# PM-BAT_v1_0-35X22_86.net
KiCad netlist of a schematic drawn in EAGLE
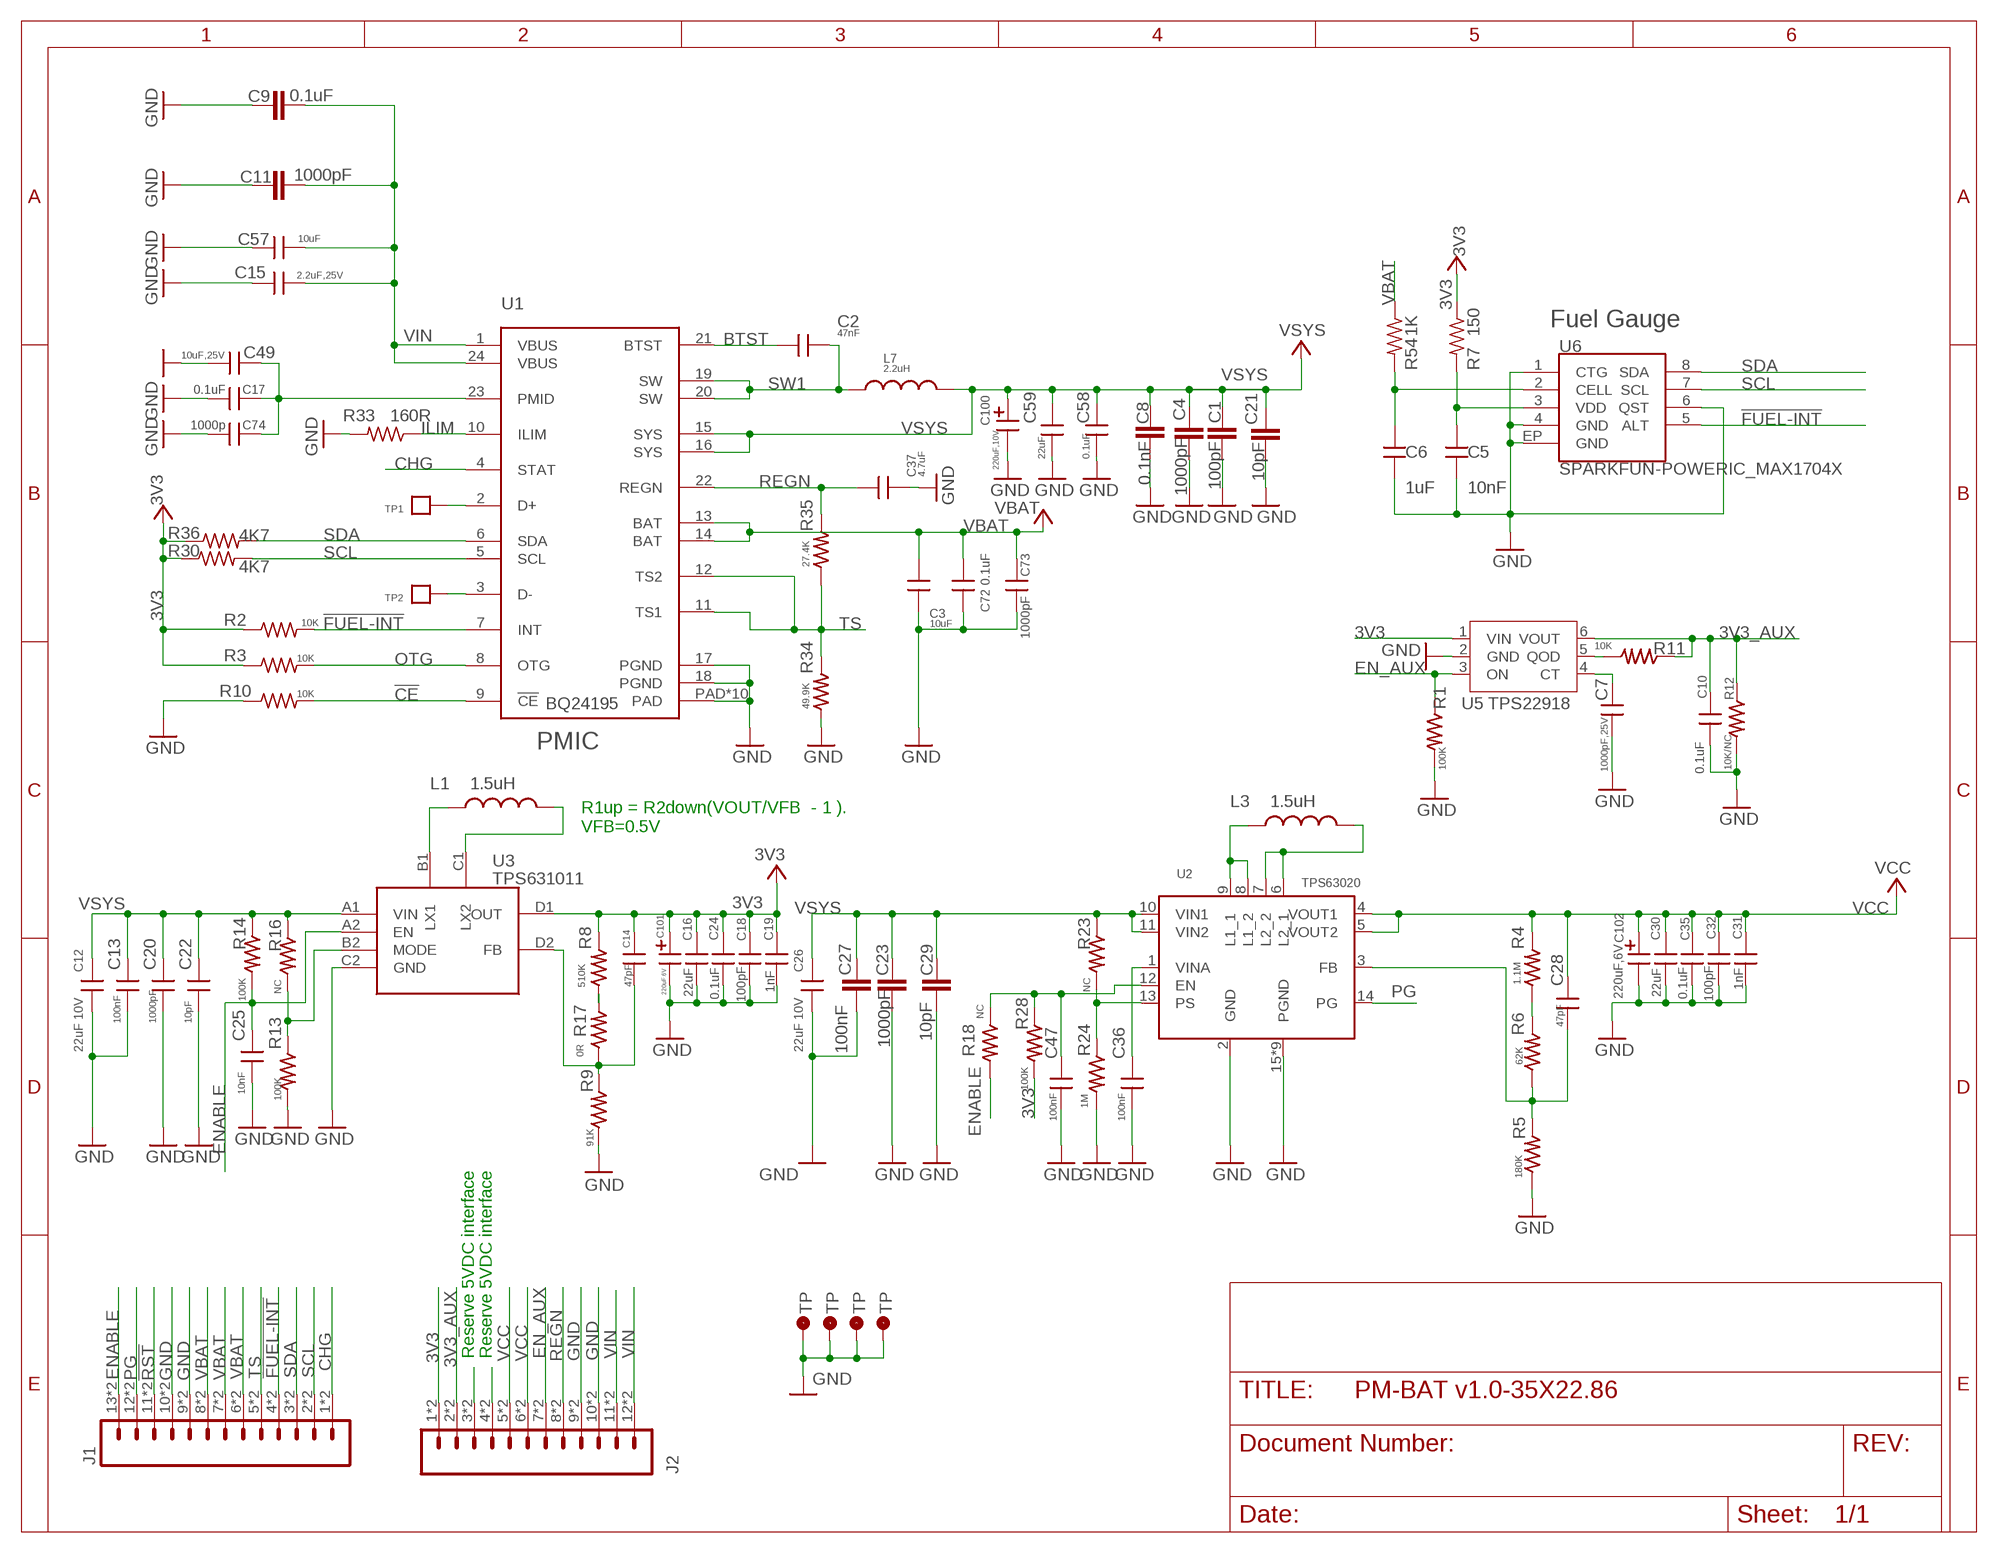
[diagram p0: schematic, sheet 1]

(export (version "E")
  (design (tool "Eeschema 10.0.6"))
  (components
    (comp (ref "C1")
      (value "100pF")
      (footprint "eagle-import:C0402_B")
      (libsource (lib "eagle-import") (part "CAP_1"))
    )
    (comp (ref "C2")
      (value "47nF")
      (footprint "eagle-import:C-0402")
      (libsource (lib "eagle-import") (part "particle SZ_CAP0402"))
    )
    (comp (ref "C3")
      (value "10uF")
      (footprint "eagle-import:C0805")
      (libsource (lib "eagle-import") (part "particle SZ_CAPC0805"))
    )
    (comp (ref "C4")
      (value "1000pF")
      (footprint "eagle-import:C0402_B")
      (libsource (lib "eagle-import") (part "CAP_1"))
    )
    (comp (ref "C5")
      (value "10nF")
      (footprint "eagle-import:C0402")
      (libsource (lib "eagle-import") (part "particle SZ_CAP0402A"))
    )
    (comp (ref "C6")
      (value "1uF")
      (footprint "eagle-import:C0402")
      (libsource (lib "eagle-import") (part "particle SZ_CAP0402A"))
    )
    (comp (ref "C7")
      (value "1000pF,25V")
      (footprint "eagle-import:C0402")
      (libsource (lib "eagle-import") (part "particle SZ_CAP0402A"))
    )
    (comp (ref "C8")
      (value "0.1nF")
      (footprint "eagle-import:C0402_B")
      (libsource (lib "eagle-import") (part "CAP_1"))
    )
    (comp (ref "C9")
      (value "0.1uF")
      (footprint "eagle-import:C0402_B")
      (libsource (lib "eagle-import") (part "CAP_1"))
    )
    (comp (ref "C10")
      (value "0.1uF")
      (footprint "eagle-import:C0201-N")
      (libsource (lib "eagle-import") (part "CAPC0201-N"))
    )
    (comp (ref "C11")
      (value "1000pF")
      (footprint "eagle-import:C0402_B")
      (libsource (lib "eagle-import") (part "CAP_1"))
    )
    (comp (ref "C12")
      (value "22uF 10V")
      (footprint "eagle-import:C0603")
      (libsource (lib "eagle-import") (part "particle SZ_21650216_CAPC0603"))
    )
    (comp (ref "C13")
      (value "100nF")
      (footprint "eagle-import:C0201-N")
      (libsource (lib "eagle-import") (part "CAPC0201-N"))
    )
    (comp (ref "C14")
      (value "47pF")
      (footprint "eagle-import:C0201-N")
      (libsource (lib "eagle-import") (part "CAPC0201-N"))
    )
    (comp (ref "C15")
      (value "2.2uF,25V")
      (footprint "eagle-import:C-0603A")
      (libsource (lib "eagle-import") (part "particle SZ_CAP0603A"))
    )
    (comp (ref "C16")
      (value "22uF")
      (footprint "eagle-import:C-0603A")
      (libsource (lib "eagle-import") (part "particle SZ_21650216_CAP0603A"))
    )
    (comp (ref "C17")
      (value "0.1uF")
      (footprint "eagle-import:C0402")
      (libsource (lib "eagle-import") (part "CAP0402A"))
    )
    (comp (ref "C18")
      (value "100pF")
      (footprint "eagle-import:C0402")
      (libsource (lib "eagle-import") (part "particle SZ_CAP0402A"))
    )
    (comp (ref "C19")
      (value "1nF")
      (footprint "eagle-import:C0402")
      (libsource (lib "eagle-import") (part "particle SZ_CAP0402A"))
    )
    (comp (ref "C20")
      (value "1000pF")
      (footprint "eagle-import:C0201-N")
      (libsource (lib "eagle-import") (part "CAPC0201-N"))
    )
    (comp (ref "C21")
      (value "10pF")
      (footprint "eagle-import:C0402_B")
      (libsource (lib "eagle-import") (part "CAP_1"))
    )
    (comp (ref "C22")
      (value "10pF")
      (footprint "eagle-import:C0201-N")
      (libsource (lib "eagle-import") (part "CAPC0201-N"))
    )
    (comp (ref "C23")
      (value "1000pF")
      (footprint "eagle-import:C0402_B")
      (libsource (lib "eagle-import") (part "CAP_1"))
    )
    (comp (ref "C24")
      (value "0.1uF")
      (footprint "eagle-import:C0402")
      (libsource (lib "eagle-import") (part "particle SZ_CAP0402A"))
    )
    (comp (ref "C25")
      (value "10nF")
      (footprint "eagle-import:C0201-N")
      (libsource (lib "eagle-import") (part "CAPC0201-N"))
    )
    (comp (ref "C26")
      (value "22uF 10V")
      (footprint "eagle-import:C0603")
      (libsource (lib "eagle-import") (part "particle SZ_21650216_CAPC0603"))
    )
    (comp (ref "C27")
      (value "100nF")
      (footprint "eagle-import:C0402_B")
      (libsource (lib "eagle-import") (part "CAP_1"))
    )
    (comp (ref "C28")
      (value "47pF")
      (footprint "eagle-import:C0201-N")
      (libsource (lib "eagle-import") (part "CAPC0201-N"))
    )
    (comp (ref "C29")
      (value "10pF")
      (footprint "eagle-import:C0402_B")
      (libsource (lib "eagle-import") (part "CAP_1"))
    )
    (comp (ref "C30")
      (value "22uF")
      (footprint "eagle-import:C-0603A")
      (libsource (lib "eagle-import") (part "particle SZ_21650216_CAP0603A"))
    )
    (comp (ref "C31")
      (value "1nF")
      (footprint "eagle-import:C0402")
      (libsource (lib "eagle-import") (part "particle SZ_CAP0402A"))
    )
    (comp (ref "C32")
      (value "100pF")
      (footprint "eagle-import:C0402")
      (libsource (lib "eagle-import") (part "particle SZ_CAP0402A"))
    )
    (comp (ref "C35")
      (value "0.1uF")
      (footprint "eagle-import:C0402")
      (libsource (lib "eagle-import") (part "particle SZ_CAP0402A"))
    )
    (comp (ref "C36")
      (value "100nF")
      (footprint "eagle-import:C0201-N")
      (libsource (lib "eagle-import") (part "CAPC0201-N"))
    )
    (comp (ref "C37")
      (value "4.7uF")
      (footprint "eagle-import:C0402")
      (libsource (lib "eagle-import") (part "particle SZ_CAP0402A"))
    )
    (comp (ref "C47")
      (value "100nF")
      (footprint "eagle-import:C0201-N")
      (libsource (lib "eagle-import") (part "CAPC0201-N"))
    )
    (comp (ref "C49")
      (value "10uF,25V")
      (footprint "eagle-import:C-0603A")
      (libsource (lib "eagle-import") (part "particle SZ_CAP0603A"))
    )
    (comp (ref "C57")
      (value "10uF")
      (footprint "eagle-import:C-0603A")
      (libsource (lib "eagle-import") (part "particle SZ_CAP0603A"))
    )
    (comp (ref "C58")
      (value "0.1uF")
      (footprint "eagle-import:C0402")
      (libsource (lib "eagle-import") (part "particle SZ_CAP0402A"))
    )
    (comp (ref "C59")
      (value "22uF")
      (footprint "eagle-import:C0603")
      (libsource (lib "eagle-import") (part "particle SZ_CAPC0603"))
    )
    (comp (ref "C72")
      (value "0.1uF")
      (footprint "eagle-import:C-0402")
      (libsource (lib "eagle-import") (part "particle SZ_CAP0402"))
    )
    (comp (ref "C73")
      (value "1000pF")
      (footprint "eagle-import:C-0402")
      (libsource (lib "eagle-import") (part "particle SZ_CAP0402"))
    )
    (comp (ref "C74")
      (value "1000p")
      (footprint "eagle-import:C-0402")
      (libsource (lib "eagle-import") (part "particle SZ_CAP0402"))
    )
    (comp (ref "C100")
      (value "220uF,10V")
      (footprint "eagle-import:CASE-B")
      (libsource (lib "eagle-import") (part "CAP-ECASE_B"))
    )
    (comp (ref "C101")
      (value "220uF.6V")
      (footprint "eagle-import:CASE-B")
      (libsource (lib "eagle-import") (part "CAP-ECASE_B"))
    )
    (comp (ref "C102")
      (value "220uF,6V")
      (footprint "eagle-import:CASE-B")
      (libsource (lib "eagle-import") (part "CAP-ECASE_B"))
    )
    (comp (ref "J1")
      (value "M13PTH-CST-R")
      (footprint "eagle-import:1X13-CASTELLATED")
      (libsource (lib "eagle-import") (part "M13PTH-CST-R"))
    )
    (comp (ref "J2")
      (value "M12PTH-CST-R")
      (footprint "eagle-import:1X12-CASTELLATED")
      (libsource (lib "eagle-import") (part "M12PTH-CST-R"))
    )
    (comp (ref "L1")
      (value "1.5uH")
      (footprint "eagle-import:INDUCTOR-2520")
      (libsource (lib "eagle-import") (part "INDUCTOR-SPARKFUNINDUCTOR-2520"))
    )
    (comp (ref "L3")
      (value "1.5uH")
      (footprint "eagle-import:INDUCTOR-2520")
      (libsource (lib "eagle-import") (part "INDUCTOR-SPARKFUNINDUCTOR-2520"))
    )
    (comp (ref "L7")
      (value "2.2uH")
      (footprint "eagle-import:INDUCTOR-4040")
      (libsource (lib "eagle-import") (part "INDUCTORI"))
    )
    (comp (ref "R1")
      (value "100K")
      (footprint "eagle-import:R0201-N")
      (libsource (lib "eagle-import") (part "RESR0201-N"))
    )
    (comp (ref "R2")
      (value "10K")
      (footprint "eagle-import:R0402_B")
      (libsource (lib "eagle-import") (part "Spark_R-US_"))
    )
    (comp (ref "R3")
      (value "10K")
      (footprint "eagle-import:R0402_B")
      (libsource (lib "eagle-import") (part "Spark_R-US_"))
    )
    (comp (ref "R4")
      (value "1.1M")
      (footprint "eagle-import:R0201-N")
      (libsource (lib "eagle-import") (part "RESR0201-N"))
    )
    (comp (ref "R5")
      (value "180K")
      (footprint "eagle-import:R0201-N")
      (libsource (lib "eagle-import") (part "RESR0201-N"))
    )
    (comp (ref "R6")
      (value "62K")
      (footprint "eagle-import:R0201-N")
      (libsource (lib "eagle-import") (part "RESR0201-N"))
    )
    (comp (ref "R7")
      (value "150")
      (footprint "eagle-import:R0402_B")
      (libsource (lib "eagle-import") (part "R-US_"))
    )
    (comp (ref "R8")
      (value "510K")
      (footprint "eagle-import:R0201-N")
      (libsource (lib "eagle-import") (part "RESR0201-N"))
    )
    (comp (ref "R9")
      (value "91K")
      (footprint "eagle-import:R0201-N")
      (libsource (lib "eagle-import") (part "RESR0201-N"))
    )
    (comp (ref "R10")
      (value "10K")
      (footprint "eagle-import:R0402_B")
      (libsource (lib "eagle-import") (part "Spark_R-US_"))
    )
    (comp (ref "R11")
      (value "10K")
      (footprint "eagle-import:R0201-N")
      (libsource (lib "eagle-import") (part "RESR0201-N"))
    )
    (comp (ref "R12")
      (value "10K/NC")
      (footprint "eagle-import:R0201-N")
      (libsource (lib "eagle-import") (part "RESR0201-N"))
    )
    (comp (ref "R13")
      (value "100K")
      (footprint "eagle-import:R0201-N")
      (libsource (lib "eagle-import") (part "RESR0201-N"))
    )
    (comp (ref "R14")
      (value "100K")
      (footprint "eagle-import:R0201-N")
      (libsource (lib "eagle-import") (part "RESR0201-N"))
    )
    (comp (ref "R16")
      (value "NC")
      (footprint "eagle-import:R0201-N")
      (libsource (lib "eagle-import") (part "RESR0201-N"))
    )
    (comp (ref "R17")
      (value "0R")
      (footprint "eagle-import:R0201-N")
      (libsource (lib "eagle-import") (part "RESR0201-N"))
    )
    (comp (ref "R18")
      (value "NC")
      (footprint "eagle-import:R0201-N")
      (libsource (lib "eagle-import") (part "RESR0201-N"))
    )
    (comp (ref "R23")
      (value "NC")
      (footprint "eagle-import:R0201-N")
      (libsource (lib "eagle-import") (part "RESR0201-N"))
    )
    (comp (ref "R24")
      (value "1M")
      (footprint "eagle-import:R0201-N")
      (libsource (lib "eagle-import") (part "RESR0201-N"))
    )
    (comp (ref "R28")
      (value "100K")
      (footprint "eagle-import:R0201-N")
      (libsource (lib "eagle-import") (part "RESR0201-N"))
    )
    (comp (ref "R30")
      (value "4K7")
      (footprint "eagle-import:R0402_B")
      (libsource (lib "eagle-import") (part "R-US_"))
    )
    (comp (ref "R33")
      (value "160R")
      (footprint "eagle-import:R0402_B")
      (libsource (lib "eagle-import") (part "R-US_"))
    )
    (comp (ref "R34")
      (value "49.9K")
      (footprint "eagle-import:R0201-N")
      (libsource (lib "eagle-import") (part "RESR0201-N"))
    )
    (comp (ref "R35")
      (value "27.4K")
      (footprint "eagle-import:R0201-N")
      (libsource (lib "eagle-import") (part "RESR0201-N"))
    )
    (comp (ref "R36")
      (value "4K7")
      (footprint "eagle-import:R0402_B")
      (libsource (lib "eagle-import") (part "R-US_"))
    )
    (comp (ref "R54")
      (value "1K")
      (footprint "eagle-import:R0402_B")
      (libsource (lib "eagle-import") (part "R-US_"))
    )
    (comp (ref "TP1")
      (value "TP1311MM")
      (footprint "eagle-import:TP-1311MM")
      (libsource (lib "eagle-import") (part "TP1311MM"))
    )
    (comp (ref "TP2")
      (value "TP1311MM")
      (footprint "eagle-import:TP-1311MM")
      (libsource (lib "eagle-import") (part "TP1311MM"))
    )
    (comp (ref "U$1")
      (value "TP")
      (footprint "eagle-import:TP_2.33X1.37")
      (libsource (lib "eagle-import") (part "TP"))
    )
    (comp (ref "U$2")
      (value "TP")
      (footprint "eagle-import:TP_2.33X1.37")
      (libsource (lib "eagle-import") (part "TP"))
    )
    (comp (ref "U$4")
      (value "TP")
      (footprint "eagle-import:TP_2.33X1.37")
      (libsource (lib "eagle-import") (part "TP"))
    )
    (comp (ref "U$5")
      (value "TP")
      (footprint "eagle-import:TP_2.33X1.37")
      (libsource (lib "eagle-import") (part "TP"))
    )
    (comp (ref "U1")
      (value "BQ24195")
      (footprint "eagle-import:ELECTRON_QFN24")
      (libsource (lib "eagle-import") (part "ELECTRON_BQ24298RTWR"))
    )
    (comp (ref "U2")
      (value "TPS63020")
      (footprint "eagle-import:TPS63020")
      (libsource (lib "eagle-import") (part "TPS63020"))
    )
    (comp (ref "U3")
      (value "TPS631011")
      (footprint "eagle-import:DSBGA")
      (libsource (lib "eagle-import") (part "TPS631010"))
    )
    (comp (ref "U5")
      (value "TPS22918")
      (footprint "eagle-import:SOT-23-6")
      (libsource (lib "eagle-import") (part "TPS22918"))
    )
    (comp (ref "U6")
      (value "SPARKFUN-POWERIC_MAX1704X")
      (footprint "eagle-import:SPARKFUN-POWERIC_TDFN-8")
      (libsource (lib "eagle-import") (part "SPARKFUN-POWERIC_MAX1704X"))
    )
  )
  (nets
    (net (code "1") (name "/3V3_AUX") (class "Default")
      (node (ref "C10") (pin "1") (pinfunction "1_1") (pintype "bidirectional"))
      (node (ref "J2") (pin "2") (pinfunction "2_2") (pintype "passive"))
      (node (ref "J2") (pin "@2") (pinfunction "2_@2") (pintype "passive"))
      (node (ref "R11") (pin "1") (pinfunction "1_1") (pintype "bidirectional"))
      (node (ref "R12") (pin "1") (pinfunction "1_1") (pintype "bidirectional"))
      (node (ref "U5") (pin "6") (pinfunction "VOUT_6") (pintype "bidirectional"))
    )
    (net (code "2") (name "/BTST") (class "Default")
      (node (ref "C2") (pin "1") (pinfunction "1_1") (pintype "bidirectional"))
      (node (ref "U1") (pin "21") (pinfunction "BTST_21") (pintype "bidirectional"))
    )
    (net (code "3") (name "/CHG") (class "Default")
      (node (ref "J1") (pin "1") (pinfunction "1_1") (pintype "passive"))
      (node (ref "J1") (pin "@1") (pinfunction "1_@1") (pintype "passive"))
      (node (ref "U1") (pin "4") (pinfunction "STAT_4") (pintype "bidirectional"))
    )
    (net (code "4") (name "/ENABLE") (class "Default")
      (node (ref "C25") (pin "1") (pinfunction "1_1") (pintype "bidirectional"))
      (node (ref "J1") (pin "13") (pinfunction "13_13") (pintype "passive"))
      (node (ref "J1") (pin "@13") (pinfunction "13_@13") (pintype "passive"))
      (node (ref "R14") (pin "2") (pinfunction "2_2") (pintype "bidirectional"))
      (node (ref "R18") (pin "2") (pinfunction "2_2") (pintype "bidirectional"))
      (node (ref "U3") (pin "A2") (pinfunction "EN_A2") (pintype "bidirectional"))
    )
    (net (code "5") (name "/EN_AUX") (class "Default")
      (node (ref "J2") (pin "7") (pinfunction "7_7") (pintype "passive"))
      (node (ref "J2") (pin "@7") (pinfunction "7_@7") (pintype "passive"))
      (node (ref "R1") (pin "1") (pinfunction "1_1") (pintype "bidirectional"))
      (node (ref "U5") (pin "3") (pinfunction "ON_3") (pintype "bidirectional"))
    )
    (net (code "6") (name "/ILIM") (class "Default")
      (node (ref "R33") (pin "1") (pinfunction "1_1") (pintype "passive"))
      (node (ref "U1") (pin "10") (pinfunction "ILIM_10") (pintype "output"))
    )
    (net (code "7") (name "/OTG") (class "Default")
      (node (ref "R3") (pin "2") (pinfunction "2_2") (pintype "passive"))
      (node (ref "U1") (pin "8") (pinfunction "OTG_8") (pintype "bidirectional"))
    )
    (net (code "8") (name "/PG") (class "Default")
      (node (ref "J1") (pin "12") (pinfunction "12_12") (pintype "passive"))
      (node (ref "J1") (pin "@12") (pinfunction "12_@12") (pintype "passive"))
      (node (ref "U2") (pin "14") (pinfunction "PG_14") (pintype "bidirectional"))
    )
    (net (code "9") (name "/REGN") (class "Default")
      (node (ref "C37") (pin "1") (pinfunction "1_1") (pintype "bidirectional"))
      (node (ref "J2") (pin "8") (pinfunction "8_8") (pintype "passive"))
      (node (ref "J2") (pin "@8") (pinfunction "8_@8") (pintype "passive"))
      (node (ref "R35") (pin "2") (pinfunction "2_2") (pintype "bidirectional"))
      (node (ref "U1") (pin "22") (pinfunction "REGN_22") (pintype "bidirectional"))
    )
    (net (code "10") (name "/SCL") (class "Default")
      (node (ref "J1") (pin "2") (pinfunction "2_2") (pintype "passive"))
      (node (ref "J1") (pin "@2") (pinfunction "2_@2") (pintype "passive"))
      (node (ref "R30") (pin "2") (pinfunction "2_2") (pintype "passive"))
      (node (ref "U1") (pin "5") (pinfunction "SCL_5") (pintype "output"))
      (node (ref "U6") (pin "7") (pinfunction "SCL_7") (pintype "bidirectional"))
    )
    (net (code "11") (name "/SDA") (class "Default")
      (node (ref "J1") (pin "3") (pinfunction "3_3") (pintype "passive"))
      (node (ref "J1") (pin "@3") (pinfunction "3_@3") (pintype "passive"))
      (node (ref "R36") (pin "2") (pinfunction "2_2") (pintype "passive"))
      (node (ref "U1") (pin "6") (pinfunction "SDA_6") (pintype "bidirectional"))
      (node (ref "U6") (pin "8") (pinfunction "SDA_8") (pintype "bidirectional"))
    )
    (net (code "12") (name "/SW1") (class "Default")
      (node (ref "C2") (pin "2") (pinfunction "2_2") (pintype "bidirectional"))
      (node (ref "L7") (pin "P$1") (pinfunction "1_P$1") (pintype "passive"))
      (node (ref "U1") (pin "19") (pinfunction "SW_19") (pintype "power_in"))
      (node (ref "U1") (pin "20") (pinfunction "SW_20") (pintype "power_in"))
    )
    (net (code "13") (name "/TS") (class "Default")
      (node (ref "J1") (pin "5") (pinfunction "5_5") (pintype "passive"))
      (node (ref "J1") (pin "@5") (pinfunction "5_@5") (pintype "passive"))
      (node (ref "R34") (pin "2") (pinfunction "2_2") (pintype "bidirectional"))
      (node (ref "R35") (pin "1") (pinfunction "1_1") (pintype "bidirectional"))
      (node (ref "U1") (pin "11") (pinfunction "TS1_11") (pintype "bidirectional"))
      (node (ref "U1") (pin "12") (pinfunction "TS2_12") (pintype "bidirectional"))
    )
    (net (code "14") (name "/VIN") (class "Default")
      (node (ref "C11") (pin "2") (pinfunction "P$2_2") (pintype "passive"))
      (node (ref "C15") (pin "1") (pinfunction "1_1") (pintype "bidirectional"))
      (node (ref "C57") (pin "1") (pinfunction "1_1") (pintype "bidirectional"))
      (node (ref "C9") (pin "2") (pinfunction "P$2_2") (pintype "passive"))
      (node (ref "J2") (pin "11") (pinfunction "11_11") (pintype "passive"))
      (node (ref "J2") (pin "12") (pinfunction "12_12") (pintype "passive"))
      (node (ref "J2") (pin "@11") (pinfunction "11_@11") (pintype "passive"))
      (node (ref "J2") (pin "@12") (pinfunction "12_@12") (pintype "passive"))
      (node (ref "U1") (pin "1") (pinfunction "VBUS_1") (pintype "power_in"))
      (node (ref "U1") (pin "24") (pinfunction "VBUS_24") (pintype "passive"))
    )
    (net (code "15") (name "/~{CE}") (class "Default")
      (node (ref "R10") (pin "2") (pinfunction "2_2") (pintype "passive"))
      (node (ref "U1") (pin "9") (pinfunction "~{CE}_9") (pintype "output"))
    )
    (net (code "16") (name "/~{FUEL-INT}") (class "Default")
      (node (ref "J1") (pin "4") (pinfunction "4_4") (pintype "passive"))
      (node (ref "J1") (pin "@4") (pinfunction "4_@4") (pintype "passive"))
      (node (ref "R2") (pin "2") (pinfunction "2_2") (pintype "passive"))
      (node (ref "U1") (pin "7") (pinfunction "INT_7") (pintype "bidirectional"))
      (node (ref "U6") (pin "5") (pinfunction "ALT_5") (pintype "bidirectional"))
    )
    (net (code "17") (name "/~{RST}") (class "Default")
      (node (ref "J1") (pin "11") (pinfunction "11_11") (pintype "passive"))
      (node (ref "J1") (pin "@11") (pinfunction "11_@11") (pintype "passive"))
    )
    (net (code "18") (name "3V3") (class "Default")
      (node (ref "C101") (pin "P$1") (pinfunction "1_P$1") (pintype "bidirectional"))
      (node (ref "C14") (pin "1") (pinfunction "1_1") (pintype "bidirectional"))
      (node (ref "C16") (pin "1") (pinfunction "1_1") (pintype "bidirectional"))
      (node (ref "C18") (pin "1") (pinfunction "1_1") (pintype "bidirectional"))
      (node (ref "C19") (pin "1") (pinfunction "1_1") (pintype "bidirectional"))
      (node (ref "C24") (pin "1") (pinfunction "1_1") (pintype "bidirectional"))
      (node (ref "J2") (pin "1") (pinfunction "1_1") (pintype "passive"))
      (node (ref "J2") (pin "@1") (pinfunction "1_@1") (pintype "passive"))
      (node (ref "R2") (pin "1") (pinfunction "1_1") (pintype "passive"))
      (node (ref "R28") (pin "2") (pinfunction "2_2") (pintype "bidirectional"))
      (node (ref "R3") (pin "1") (pinfunction "1_1") (pintype "passive"))
      (node (ref "R30") (pin "1") (pinfunction "1_1") (pintype "passive"))
      (node (ref "R36") (pin "1") (pinfunction "1_1") (pintype "passive"))
      (node (ref "R7") (pin "1") (pinfunction "1_1") (pintype "passive"))
      (node (ref "R8") (pin "2") (pinfunction "2_2") (pintype "bidirectional"))
      (node (ref "U3") (pin "D1") (pinfunction "OUT_D1") (pintype "bidirectional"))
      (node (ref "U5") (pin "1") (pinfunction "VIN_1") (pintype "bidirectional"))
    )
    (net (code "19") (name "GND") (class "Default")
      (node (ref "C1") (pin "1") (pinfunction "P$1_1") (pintype "passive"))
      (node (ref "C10") (pin "2") (pinfunction "2_2") (pintype "bidirectional"))
      (node (ref "C100") (pin "P$2") (pinfunction "2_P$2") (pintype "bidirectional"))
      (node (ref "C101") (pin "P$2") (pinfunction "2_P$2") (pintype "bidirectional"))
      (node (ref "C102") (pin "P$2") (pinfunction "2_P$2") (pintype "bidirectional"))
      (node (ref "C11") (pin "1") (pinfunction "P$1_1") (pintype "passive"))
      (node (ref "C12") (pin "2") (pinfunction "2_2") (pintype "bidirectional"))
      (node (ref "C13") (pin "2") (pinfunction "2_2") (pintype "bidirectional"))
      (node (ref "C15") (pin "2") (pinfunction "2_2") (pintype "bidirectional"))
      (node (ref "C16") (pin "2") (pinfunction "2_2") (pintype "bidirectional"))
      (node (ref "C17") (pin "1") (pinfunction "1_1") (pintype "bidirectional"))
      (node (ref "C18") (pin "2") (pinfunction "2_2") (pintype "bidirectional"))
      (node (ref "C19") (pin "2") (pinfunction "2_2") (pintype "bidirectional"))
      (node (ref "C20") (pin "2") (pinfunction "2_2") (pintype "bidirectional"))
      (node (ref "C21") (pin "1") (pinfunction "P$1_1") (pintype "passive"))
      (node (ref "C22") (pin "2") (pinfunction "2_2") (pintype "bidirectional"))
      (node (ref "C23") (pin "1") (pinfunction "P$1_1") (pintype "passive"))
      (node (ref "C24") (pin "2") (pinfunction "2_2") (pintype "bidirectional"))
      (node (ref "C25") (pin "2") (pinfunction "2_2") (pintype "bidirectional"))
      (node (ref "C26") (pin "2") (pinfunction "2_2") (pintype "bidirectional"))
      (node (ref "C27") (pin "1") (pinfunction "P$1_1") (pintype "passive"))
      (node (ref "C29") (pin "1") (pinfunction "P$1_1") (pintype "passive"))
      (node (ref "C3") (pin "2") (pinfunction "2_2") (pintype "bidirectional"))
      (node (ref "C30") (pin "2") (pinfunction "2_2") (pintype "bidirectional"))
      (node (ref "C31") (pin "2") (pinfunction "2_2") (pintype "bidirectional"))
      (node (ref "C32") (pin "2") (pinfunction "2_2") (pintype "bidirectional"))
      (node (ref "C35") (pin "2") (pinfunction "2_2") (pintype "bidirectional"))
      (node (ref "C36") (pin "2") (pinfunction "2_2") (pintype "bidirectional"))
      (node (ref "C37") (pin "2") (pinfunction "2_2") (pintype "bidirectional"))
      (node (ref "C4") (pin "1") (pinfunction "P$1_1") (pintype "passive"))
      (node (ref "C47") (pin "2") (pinfunction "2_2") (pintype "bidirectional"))
      (node (ref "C49") (pin "2") (pinfunction "2_2") (pintype "bidirectional"))
      (node (ref "C5") (pin "2") (pinfunction "2_2") (pintype "bidirectional"))
      (node (ref "C57") (pin "2") (pinfunction "2_2") (pintype "bidirectional"))
      (node (ref "C58") (pin "2") (pinfunction "2_2") (pintype "bidirectional"))
      (node (ref "C59") (pin "2") (pinfunction "2_2") (pintype "bidirectional"))
      (node (ref "C6") (pin "2") (pinfunction "2_2") (pintype "bidirectional"))
      (node (ref "C7") (pin "2") (pinfunction "2_2") (pintype "bidirectional"))
      (node (ref "C72") (pin "2") (pinfunction "2_2") (pintype "bidirectional"))
      (node (ref "C73") (pin "2") (pinfunction "2_2") (pintype "bidirectional"))
      (node (ref "C74") (pin "1") (pinfunction "1_1") (pintype "bidirectional"))
      (node (ref "C8") (pin "1") (pinfunction "P$1_1") (pintype "passive"))
      (node (ref "C9") (pin "1") (pinfunction "P$1_1") (pintype "passive"))
      (node (ref "J1") (pin "10") (pinfunction "10_10") (pintype "passive"))
      (node (ref "J1") (pin "9") (pinfunction "9_9") (pintype "passive"))
      (node (ref "J1") (pin "@10") (pinfunction "10_@10") (pintype "passive"))
      (node (ref "J1") (pin "@9") (pinfunction "9_@9") (pintype "passive"))
      (node (ref "J2") (pin "10") (pinfunction "10_10") (pintype "passive"))
      (node (ref "J2") (pin "9") (pinfunction "9_9") (pintype "passive"))
      (node (ref "J2") (pin "@10") (pinfunction "10_@10") (pintype "passive"))
      (node (ref "J2") (pin "@9") (pinfunction "9_@9") (pintype "passive"))
      (node (ref "R1") (pin "2") (pinfunction "2_2") (pintype "bidirectional"))
      (node (ref "R10") (pin "1") (pinfunction "1_1") (pintype "passive"))
      (node (ref "R12") (pin "2") (pinfunction "2_2") (pintype "bidirectional"))
      (node (ref "R13") (pin "2") (pinfunction "2_2") (pintype "bidirectional"))
      (node (ref "R24") (pin "2") (pinfunction "2_2") (pintype "bidirectional"))
      (node (ref "R33") (pin "2") (pinfunction "2_2") (pintype "passive"))
      (node (ref "R34") (pin "1") (pinfunction "1_1") (pintype "bidirectional"))
      (node (ref "R5") (pin "1") (pinfunction "1_1") (pintype "bidirectional"))
      (node (ref "R9") (pin "1") (pinfunction "1_1") (pintype "bidirectional"))
      (node (ref "U$1") (pin "1") (pinfunction "TP_1") (pintype "bidirectional"))
      (node (ref "U$2") (pin "1") (pinfunction "TP_1") (pintype "bidirectional"))
      (node (ref "U$4") (pin "1") (pinfunction "TP_1") (pintype "bidirectional"))
      (node (ref "U$5") (pin "1") (pinfunction "TP_1") (pintype "bidirectional"))
      (node (ref "U1") (pin "17") (pinfunction "PGND_17") (pintype "passive"))
      (node (ref "U1") (pin "18") (pinfunction "PGND_18") (pintype "passive"))
      (node (ref "U1") (pin "PAD") (pinfunction "PAD_PAD") (pintype "power_in"))
      (node (ref "U1") (pin "PAD@1") (pinfunction "PAD_PAD@1") (pintype "power_in"))
      (node (ref "U1") (pin "PAD@2") (pinfunction "PAD_PAD@2") (pintype "power_in"))
      (node (ref "U1") (pin "PAD@3") (pinfunction "PAD_PAD@3") (pintype "power_in"))
      (node (ref "U1") (pin "PAD@4") (pinfunction "PAD_PAD@4") (pintype "power_in"))
      (node (ref "U1") (pin "PAD@5") (pinfunction "PAD_PAD@5") (pintype "power_in"))
      (node (ref "U1") (pin "PAD@6") (pinfunction "PAD_PAD@6") (pintype "power_in"))
      (node (ref "U1") (pin "PAD@7") (pinfunction "PAD_PAD@7") (pintype "power_in"))
      (node (ref "U1") (pin "PAD@8") (pinfunction "PAD_PAD@8") (pintype "power_in"))
      (node (ref "U1") (pin "PAD@9") (pinfunction "PAD_PAD@9") (pintype "power_in"))
      (node (ref "U2") (pin "15") (pinfunction "PGND_15") (pintype "bidirectional"))
      (node (ref "U2") (pin "16") (pinfunction "PGND_16") (pintype "bidirectional"))
      (node (ref "U2") (pin "17") (pinfunction "PGND_17") (pintype "bidirectional"))
      (node (ref "U2") (pin "18") (pinfunction "PGND_18") (pintype "bidirectional"))
      (node (ref "U2") (pin "19") (pinfunction "PGND_19") (pintype "bidirectional"))
      (node (ref "U2") (pin "2") (pinfunction "GND_2") (pintype "bidirectional"))
      (node (ref "U2") (pin "20") (pinfunction "PGND_20") (pintype "bidirectional"))
      (node (ref "U2") (pin "21") (pinfunction "PGND_21") (pintype "bidirectional"))
      (node (ref "U2") (pin "22") (pinfunction "PGND_22") (pintype "bidirectional"))
      (node (ref "U2") (pin "23") (pinfunction "PGND_23") (pintype "bidirectional"))
      (node (ref "U3") (pin "C2") (pinfunction "GND_C2") (pintype "bidirectional"))
      (node (ref "U5") (pin "2") (pinfunction "GND_2") (pintype "bidirectional"))
      (node (ref "U6") (pin "1") (pinfunction "CTG_1") (pintype "bidirectional"))
      (node (ref "U6") (pin "4") (pinfunction "GND_4") (pintype "bidirectional"))
      (node (ref "U6") (pin "6") (pinfunction "QST_6") (pintype "bidirectional"))
      (node (ref "U6") (pin "EP") (pinfunction "GND_EP") (pintype "bidirectional"))
    )
    (net (code "20") (name "Net-(J2-3-Pad@3)") (class "Default")
      (node (ref "J2") (pin "3") (pinfunction "3_3") (pintype "passive"))
      (node (ref "J2") (pin "@3") (pinfunction "3_@3") (pintype "passive"))
    )
    (net (code "21") (name "Net-(J2-4-Pad@4)") (class "Default")
      (node (ref "J2") (pin "4") (pinfunction "4_4") (pintype "passive"))
      (node (ref "J2") (pin "@4") (pinfunction "4_@4") (pintype "passive"))
    )
    (net (code "22") (name "Net-(R4-Pad1)") (class "Default")
      (node (ref "R4") (pin "1") (pinfunction "1_1") (pintype "bidirectional"))
      (node (ref "R6") (pin "2") (pinfunction "2_2") (pintype "bidirectional"))
    )
    (net (code "23") (name "Net-(R17-Pad2)") (class "Default")
      (node (ref "R17") (pin "2") (pinfunction "2_2") (pintype "bidirectional"))
      (node (ref "R8") (pin "1") (pinfunction "1_1") (pintype "bidirectional"))
    )
    (net (code "24") (name "Net-(TP1-1)") (class "Default")
      (node (ref "TP1") (pin "P$1") (pinfunction "1_P$1") (pintype "bidirectional"))
      (node (ref "U1") (pin "2") (pinfunction "D+_2") (pintype "output"))
    )
    (net (code "25") (name "Net-(TP2-1)") (class "Default")
      (node (ref "TP2") (pin "P$1") (pinfunction "1_P$1") (pintype "bidirectional"))
      (node (ref "U1") (pin "3") (pinfunction "D-_3") (pintype "output"))
    )
    (net (code "26") (name "Net-(U1-PMID)") (class "Default")
      (node (ref "C17") (pin "2") (pinfunction "2_2") (pintype "bidirectional"))
      (node (ref "C49") (pin "1") (pinfunction "1_1") (pintype "bidirectional"))
      (node (ref "C74") (pin "2") (pinfunction "2_2") (pintype "bidirectional"))
      (node (ref "U1") (pin "23") (pinfunction "PMID_23") (pintype "passive"))
    )
    (net (code "27") (name "Net-(U2-EN)") (class "Default")
      (node (ref "C47") (pin "1") (pinfunction "1_1") (pintype "bidirectional"))
      (node (ref "R18") (pin "1") (pinfunction "1_1") (pintype "bidirectional"))
      (node (ref "R28") (pin "1") (pinfunction "1_1") (pintype "bidirectional"))
      (node (ref "U2") (pin "12") (pinfunction "EN_12") (pintype "bidirectional"))
    )
    (net (code "28") (name "Net-(U2-FB)") (class "Default")
      (node (ref "C28") (pin "2") (pinfunction "2_2") (pintype "bidirectional"))
      (node (ref "R5") (pin "2") (pinfunction "2_2") (pintype "bidirectional"))
      (node (ref "R6") (pin "1") (pinfunction "1_1") (pintype "bidirectional"))
      (node (ref "U2") (pin "3") (pinfunction "FB_3") (pintype "bidirectional"))
    )
    (net (code "29") (name "Net-(U2-L1_1)") (class "Default")
      (node (ref "L3") (pin "1") (pinfunction "1_1") (pintype "passive"))
      (node (ref "U2") (pin "8") (pinfunction "L1_2_8") (pintype "bidirectional"))
      (node (ref "U2") (pin "9") (pinfunction "L1_1_9") (pintype "bidirectional"))
    )
    (net (code "30") (name "Net-(U2-L2_1)") (class "Default")
      (node (ref "L3") (pin "2") (pinfunction "2_2") (pintype "passive"))
      (node (ref "U2") (pin "6") (pinfunction "L2_1_6") (pintype "bidirectional"))
      (node (ref "U2") (pin "7") (pinfunction "L2_2_7") (pintype "bidirectional"))
    )
    (net (code "31") (name "Net-(U2-PS)") (class "Default")
      (node (ref "R23") (pin "2") (pinfunction "2_2") (pintype "bidirectional"))
      (node (ref "R24") (pin "1") (pinfunction "1_1") (pintype "bidirectional"))
      (node (ref "U2") (pin "13") (pinfunction "PS_13") (pintype "bidirectional"))
    )
    (net (code "32") (name "Net-(U2-VINA)") (class "Default")
      (node (ref "C36") (pin "1") (pinfunction "1_1") (pintype "bidirectional"))
      (node (ref "U2") (pin "1") (pinfunction "VINA_1") (pintype "bidirectional"))
    )
    (net (code "33") (name "Net-(U3-FB)") (class "Default")
      (node (ref "C14") (pin "2") (pinfunction "2_2") (pintype "bidirectional"))
      (node (ref "R17") (pin "1") (pinfunction "1_1") (pintype "bidirectional"))
      (node (ref "R9") (pin "2") (pinfunction "2_2") (pintype "bidirectional"))
      (node (ref "U3") (pin "D2") (pinfunction "FB_D2") (pintype "bidirectional"))
    )
    (net (code "34") (name "Net-(U3-LX1)") (class "Default")
      (node (ref "L1") (pin "1") (pinfunction "1_1") (pintype "passive"))
      (node (ref "U3") (pin "B1") (pinfunction "LX1_B1") (pintype "bidirectional"))
    )
    (net (code "35") (name "Net-(U3-LX2)") (class "Default")
      (node (ref "L1") (pin "2") (pinfunction "2_2") (pintype "passive"))
      (node (ref "U3") (pin "C1") (pinfunction "LX2_C1") (pintype "bidirectional"))
    )
    (net (code "36") (name "Net-(U3-MODE)") (class "Default")
      (node (ref "R13") (pin "1") (pinfunction "1_1") (pintype "bidirectional"))
      (node (ref "R16") (pin "2") (pinfunction "2_2") (pintype "bidirectional"))
      (node (ref "U3") (pin "B2") (pinfunction "MODE_B2") (pintype "bidirectional"))
    )
    (net (code "37") (name "Net-(U5-CT)") (class "Default")
      (node (ref "C7") (pin "1") (pinfunction "1_1") (pintype "bidirectional"))
      (node (ref "U5") (pin "4") (pinfunction "CT_4") (pintype "bidirectional"))
    )
    (net (code "38") (name "Net-(U5-QOD)") (class "Default")
      (node (ref "R11") (pin "2") (pinfunction "2_2") (pintype "bidirectional"))
      (node (ref "U5") (pin "5") (pinfunction "QOD_5") (pintype "bidirectional"))
    )
    (net (code "39") (name "Net-(U6-CELL)") (class "Default")
      (node (ref "C6") (pin "1") (pinfunction "1_1") (pintype "bidirectional"))
      (node (ref "R54") (pin "2") (pinfunction "2_2") (pintype "passive"))
      (node (ref "U6") (pin "2") (pinfunction "CELL_2") (pintype "bidirectional"))
    )
    (net (code "40") (name "Net-(U6-VDD)") (class "Default")
      (node (ref "C5") (pin "1") (pinfunction "1_1") (pintype "bidirectional"))
      (node (ref "R7") (pin "2") (pinfunction "2_2") (pintype "passive"))
      (node (ref "U6") (pin "3") (pinfunction "VDD_3") (pintype "bidirectional"))
    )
    (net (code "41") (name "VBAT") (class "Default")
      (node (ref "C3") (pin "1") (pinfunction "1_1") (pintype "bidirectional"))
      (node (ref "C72") (pin "1") (pinfunction "1_1") (pintype "bidirectional"))
      (node (ref "C73") (pin "1") (pinfunction "1_1") (pintype "bidirectional"))
      (node (ref "J1") (pin "6") (pinfunction "6_6") (pintype "passive"))
      (node (ref "J1") (pin "7") (pinfunction "7_7") (pintype "passive"))
      (node (ref "J1") (pin "8") (pinfunction "8_8") (pintype "passive"))
      (node (ref "J1") (pin "@6") (pinfunction "6_@6") (pintype "passive"))
      (node (ref "J1") (pin "@7") (pinfunction "7_@7") (pintype "passive"))
      (node (ref "J1") (pin "@8") (pinfunction "8_@8") (pintype "passive"))
      (node (ref "R54") (pin "1") (pinfunction "1_1") (pintype "passive"))
      (node (ref "U1") (pin "13") (pinfunction "BAT_13") (pintype "passive"))
      (node (ref "U1") (pin "14") (pinfunction "BAT_14") (pintype "power_in"))
    )
    (net (code "42") (name "VCC") (class "Default")
      (node (ref "C102") (pin "P$1") (pinfunction "1_P$1") (pintype "bidirectional"))
      (node (ref "C28") (pin "1") (pinfunction "1_1") (pintype "bidirectional"))
      (node (ref "C30") (pin "1") (pinfunction "1_1") (pintype "bidirectional"))
      (node (ref "C31") (pin "1") (pinfunction "1_1") (pintype "bidirectional"))
      (node (ref "C32") (pin "1") (pinfunction "1_1") (pintype "bidirectional"))
      (node (ref "C35") (pin "1") (pinfunction "1_1") (pintype "bidirectional"))
      (node (ref "J2") (pin "5") (pinfunction "5_5") (pintype "passive"))
      (node (ref "J2") (pin "6") (pinfunction "6_6") (pintype "passive"))
      (node (ref "J2") (pin "@5") (pinfunction "5_@5") (pintype "passive"))
      (node (ref "J2") (pin "@6") (pinfunction "6_@6") (pintype "passive"))
      (node (ref "R4") (pin "2") (pinfunction "2_2") (pintype "bidirectional"))
      (node (ref "U2") (pin "4") (pinfunction "VOUT1_4") (pintype "bidirectional"))
      (node (ref "U2") (pin "5") (pinfunction "VOUT2_5") (pintype "bidirectional"))
    )
    (net (code "43") (name "VSYS") (class "Default")
      (node (ref "C1") (pin "2") (pinfunction "P$2_2") (pintype "passive"))
      (node (ref "C100") (pin "P$1") (pinfunction "1_P$1") (pintype "bidirectional"))
      (node (ref "C12") (pin "1") (pinfunction "1_1") (pintype "bidirectional"))
      (node (ref "C13") (pin "1") (pinfunction "1_1") (pintype "bidirectional"))
      (node (ref "C20") (pin "1") (pinfunction "1_1") (pintype "bidirectional"))
      (node (ref "C21") (pin "2") (pinfunction "P$2_2") (pintype "passive"))
      (node (ref "C22") (pin "1") (pinfunction "1_1") (pintype "bidirectional"))
      (node (ref "C23") (pin "2") (pinfunction "P$2_2") (pintype "passive"))
      (node (ref "C26") (pin "1") (pinfunction "1_1") (pintype "bidirectional"))
      (node (ref "C27") (pin "2") (pinfunction "P$2_2") (pintype "passive"))
      (node (ref "C29") (pin "2") (pinfunction "P$2_2") (pintype "passive"))
      (node (ref "C4") (pin "2") (pinfunction "P$2_2") (pintype "passive"))
      (node (ref "C58") (pin "1") (pinfunction "1_1") (pintype "bidirectional"))
      (node (ref "C59") (pin "1") (pinfunction "1_1") (pintype "bidirectional"))
      (node (ref "C8") (pin "2") (pinfunction "P$2_2") (pintype "passive"))
      (node (ref "L7") (pin "P$2") (pinfunction "2_P$2") (pintype "passive"))
      (node (ref "R14") (pin "1") (pinfunction "1_1") (pintype "bidirectional"))
      (node (ref "R16") (pin "1") (pinfunction "1_1") (pintype "bidirectional"))
      (node (ref "R23") (pin "1") (pinfunction "1_1") (pintype "bidirectional"))
      (node (ref "U1") (pin "15") (pinfunction "SYS_15") (pintype "power_in"))
      (node (ref "U1") (pin "16") (pinfunction "SYS_16") (pintype "power_in"))
      (node (ref "U2") (pin "10") (pinfunction "VIN1_10") (pintype "bidirectional"))
      (node (ref "U2") (pin "11") (pinfunction "VIN2_11") (pintype "bidirectional"))
      (node (ref "U3") (pin "A1") (pinfunction "VIN_A1") (pintype "bidirectional"))
    )
  )
)
